# shield.net
KiCad netlist of a schematic drawn in EAGLE
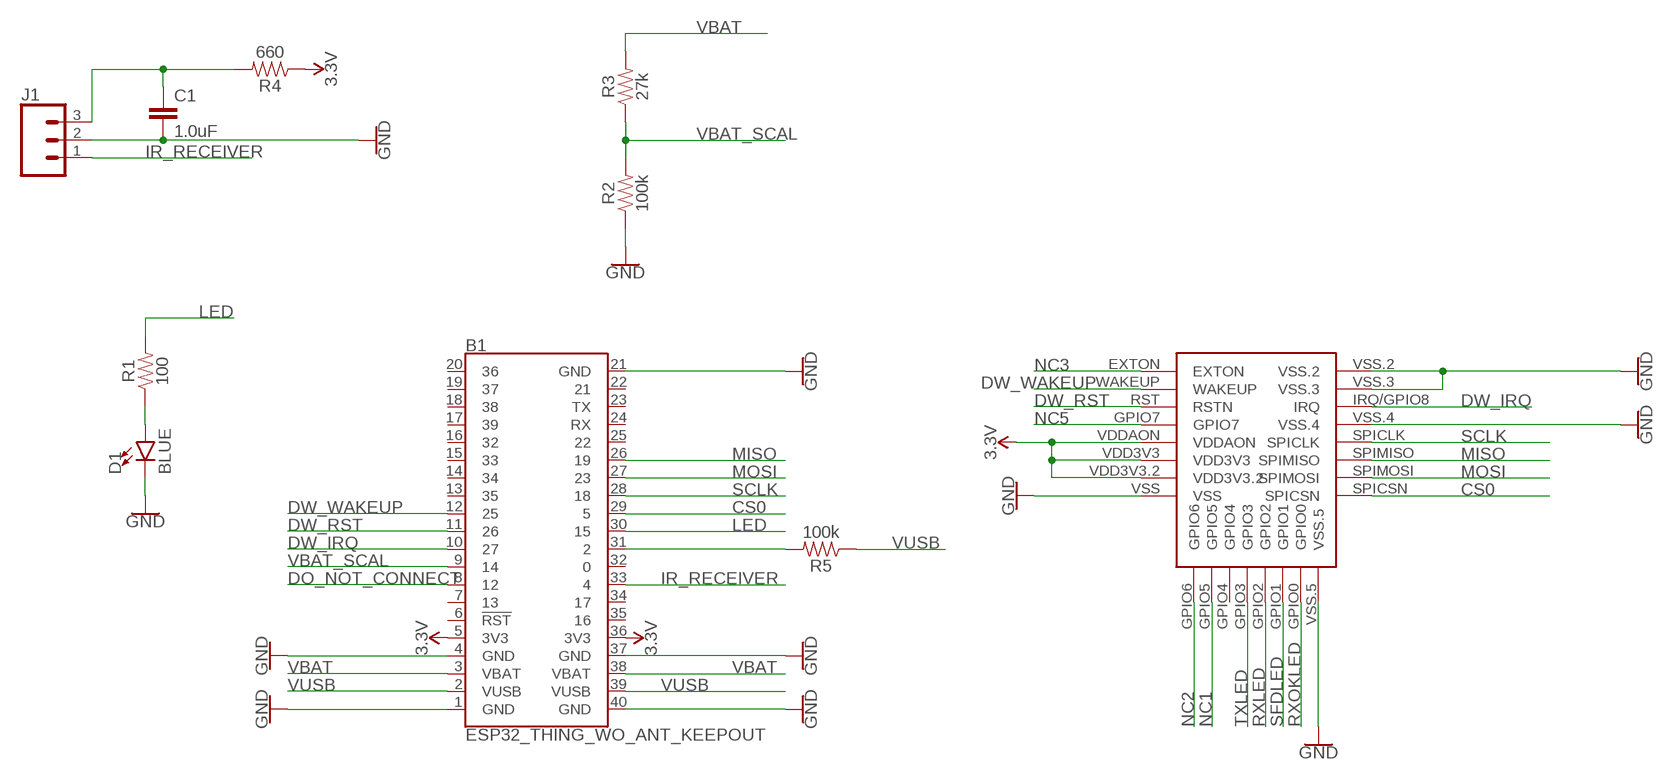
[diagram p0: schematic, sheet 1]

(export (version "E")
  (design (tool "Eeschema 10.0.6"))
  (components
    (comp (ref "B1")
      (value "ESP32_THING_WO_ANT_KEEPOUT")
      (footprint "eagle-import:ESP32_THING_NO_ANT")
      (libsource (lib "eagle-import") (part "ESP32_THING_WO_ANT_KEEPOUT"))
    )
    (comp (ref "C1")
      (value "1.0uF")
      (footprint "eagle-import:1206")
      (libsource (lib "eagle-import") (part "1.0UF-1206-50V-10%"))
    )
    (comp (ref "D1")
      (value "BLUE")
      (footprint "eagle-import:LED-1206")
      (libsource (lib "eagle-import") (part "LED-BLUE1206"))
    )
    (comp (ref "J1")
      (value "CONN_03")
      (footprint "eagle-import:1X03")
      (libsource (lib "eagle-import") (part "CONN_03"))
    )
    (comp (ref "R1")
      (value "100")
      (footprint "eagle-import:1206")
      (libsource (lib "eagle-import") (part "RESISTOR1206"))
    )
    (comp (ref "R2")
      (value "100k")
      (footprint "eagle-import:1206")
      (libsource (lib "eagle-import") (part "RESISTOR1206"))
    )
    (comp (ref "R3")
      (value "27k")
      (footprint "eagle-import:1206")
      (libsource (lib "eagle-import") (part "RESISTOR1206"))
    )
    (comp (ref "R4")
      (value "660")
      (footprint "eagle-import:1206")
      (libsource (lib "eagle-import") (part "RESISTOR1206"))
    )
    (comp (ref "R5")
      (value "100k")
      (footprint "eagle-import:1206")
      (libsource (lib "eagle-import") (part "RESISTOR1206"))
    )
    (comp (ref "U$1")
      (value "DWM1000")
      (footprint "eagle-import:DWM1000")
      (libsource (lib "eagle-import") (part "DWM1000"))
    )
  )
  (nets
    (net (code "1") (name "/CS0") (class "Default")
      (node (ref "B1") (pin "29") (pinfunction "5_29") (pintype "bidirectional"))
      (node (ref "U$1") (pin "SPICSN") (pinfunction "SPICSN_SPICSN") (pintype "bidirectional"))
    )
    (net (code "2") (name "/DO_NOT_CONNECT") (class "Default")
      (node (ref "B1") (pin "8") (pinfunction "12_8") (pintype "bidirectional"))
    )
    (net (code "3") (name "/DW_IRQ") (class "Default")
      (node (ref "B1") (pin "10") (pinfunction "27_10") (pintype "bidirectional"))
      (node (ref "U$1") (pin "IRQ/GPIO8") (pinfunction "IRQ_IRQ/GPIO8") (pintype "bidirectional"))
    )
    (net (code "4") (name "/DW_RST") (class "Default")
      (node (ref "B1") (pin "11") (pinfunction "26_11") (pintype "bidirectional"))
      (node (ref "U$1") (pin "RST") (pinfunction "RSTN_RST") (pintype "bidirectional"))
    )
    (net (code "5") (name "/DW_WAKEUP") (class "Default")
      (node (ref "B1") (pin "12") (pinfunction "25_12") (pintype "bidirectional"))
      (node (ref "U$1") (pin "WAKEUP") (pinfunction "WAKEUP_WAKEUP") (pintype "bidirectional"))
    )
    (net (code "6") (name "/IR_RECEIVER") (class "Default")
      (node (ref "B1") (pin "33") (pinfunction "4_33") (pintype "bidirectional"))
      (node (ref "J1") (pin "1") (pinfunction "1_1") (pintype "passive"))
    )
    (net (code "7") (name "/LED") (class "Default")
      (node (ref "B1") (pin "30") (pinfunction "15_30") (pintype "bidirectional"))
      (node (ref "R1") (pin "2") (pinfunction "2_2") (pintype "passive"))
    )
    (net (code "8") (name "/MISO") (class "Default")
      (node (ref "B1") (pin "26") (pinfunction "19_26") (pintype "bidirectional"))
      (node (ref "U$1") (pin "SPIMISO") (pinfunction "SPIMISO_SPIMISO") (pintype "bidirectional"))
    )
    (net (code "9") (name "/MOSI") (class "Default")
      (node (ref "B1") (pin "27") (pinfunction "23_27") (pintype "bidirectional"))
      (node (ref "U$1") (pin "SPIMOSI") (pinfunction "SPIMOSI_SPIMOSI") (pintype "bidirectional"))
    )
    (net (code "10") (name "/NC1") (class "Default")
      (node (ref "U$1") (pin "GPIO5") (pinfunction "GPIO5_GPIO5") (pintype "bidirectional"))
    )
    (net (code "11") (name "/NC2") (class "Default")
      (node (ref "U$1") (pin "GPIO6") (pinfunction "GPIO6_GPIO6") (pintype "bidirectional"))
    )
    (net (code "12") (name "/NC3") (class "Default")
      (node (ref "U$1") (pin "EXTON") (pinfunction "EXTON_EXTON") (pintype "bidirectional"))
    )
    (net (code "13") (name "/NC5") (class "Default")
      (node (ref "U$1") (pin "GPIO7") (pinfunction "GPIO7_GPIO7") (pintype "bidirectional"))
    )
    (net (code "14") (name "/RXLED") (class "Default")
      (node (ref "U$1") (pin "GPIO2") (pinfunction "GPIO2_GPIO2") (pintype "bidirectional"))
    )
    (net (code "15") (name "/RXOKLED") (class "Default")
      (node (ref "U$1") (pin "GPIO0") (pinfunction "GPIO0_GPIO0") (pintype "bidirectional"))
    )
    (net (code "16") (name "/SCLK") (class "Default")
      (node (ref "B1") (pin "28") (pinfunction "18_28") (pintype "bidirectional"))
      (node (ref "U$1") (pin "SPICLK") (pinfunction "SPICLK_SPICLK") (pintype "bidirectional"))
    )
    (net (code "17") (name "/SFDLED") (class "Default")
      (node (ref "U$1") (pin "GPIO1") (pinfunction "GPIO1_GPIO1") (pintype "bidirectional"))
    )
    (net (code "18") (name "/TXLED") (class "Default")
      (node (ref "U$1") (pin "GPIO3") (pinfunction "GPIO3_GPIO3") (pintype "bidirectional"))
    )
    (net (code "19") (name "/VBAT") (class "Default")
      (node (ref "B1") (pin "3") (pinfunction "VBAT_3") (pintype "bidirectional"))
      (node (ref "B1") (pin "38") (pinfunction "VBAT_38") (pintype "bidirectional"))
      (node (ref "R3") (pin "2") (pinfunction "2_2") (pintype "passive"))
    )
    (net (code "20") (name "/VBAT_SCAL") (class "Default")
      (node (ref "B1") (pin "9") (pinfunction "14_9") (pintype "bidirectional"))
      (node (ref "R2") (pin "2") (pinfunction "2_2") (pintype "passive"))
      (node (ref "R3") (pin "1") (pinfunction "1_1") (pintype "passive"))
    )
    (net (code "21") (name "/VUSB") (class "Default")
      (node (ref "B1") (pin "2") (pinfunction "VUSB_2") (pintype "bidirectional"))
      (node (ref "B1") (pin "39") (pinfunction "VUSB_39") (pintype "bidirectional"))
      (node (ref "R5") (pin "1") (pinfunction "1_1") (pintype "passive"))
    )
    (net (code "22") (name "3.3V") (class "Default")
      (node (ref "B1") (pin "36") (pinfunction "3V3_36") (pintype "bidirectional"))
      (node (ref "B1") (pin "5") (pinfunction "3V3_5") (pintype "bidirectional"))
      (node (ref "R4") (pin "1") (pinfunction "1_1") (pintype "passive"))
      (node (ref "U$1") (pin "VDD3V3") (pinfunction "VDD3V3_VDD3V3") (pintype "bidirectional"))
      (node (ref "U$1") (pin "VDD3V3.2") (pinfunction "VDD3V3.2_VDD3V3.2") (pintype "bidirectional"))
      (node (ref "U$1") (pin "VDDAON") (pinfunction "VDDAON_VDDAON") (pintype "bidirectional"))
    )
    (net (code "23") (name "GND") (class "Default")
      (node (ref "B1") (pin "1") (pinfunction "GND_1") (pintype "bidirectional"))
      (node (ref "B1") (pin "21") (pinfunction "GND_21") (pintype "bidirectional"))
      (node (ref "B1") (pin "37") (pinfunction "GND_37") (pintype "bidirectional"))
      (node (ref "B1") (pin "4") (pinfunction "GND_4") (pintype "bidirectional"))
      (node (ref "B1") (pin "40") (pinfunction "GND_40") (pintype "bidirectional"))
      (node (ref "C1") (pin "2") (pinfunction "2_2") (pintype "passive"))
      (node (ref "D1") (pin "C") (pinfunction "C_C") (pintype "passive"))
      (node (ref "J1") (pin "2") (pinfunction "2_2") (pintype "passive"))
      (node (ref "R2") (pin "1") (pinfunction "1_1") (pintype "passive"))
      (node (ref "U$1") (pin "VSS") (pinfunction "VSS_VSS") (pintype "bidirectional"))
      (node (ref "U$1") (pin "VSS.2") (pinfunction "VSS.2_VSS.2") (pintype "bidirectional"))
      (node (ref "U$1") (pin "VSS.3") (pinfunction "VSS.3_VSS.3") (pintype "bidirectional"))
      (node (ref "U$1") (pin "VSS.4") (pinfunction "VSS.4_VSS.4") (pintype "bidirectional"))
      (node (ref "U$1") (pin "VSS.5") (pinfunction "VSS.5_VSS.5") (pintype "bidirectional"))
    )
    (net (code "24") (name "Net-(B1-2)") (class "Default")
      (node (ref "B1") (pin "31") (pinfunction "2_31") (pintype "bidirectional"))
      (node (ref "R5") (pin "2") (pinfunction "2_2") (pintype "passive"))
    )
    (net (code "25") (name "Net-(C1-Pad1)") (class "Default")
      (node (ref "C1") (pin "1") (pinfunction "1_1") (pintype "passive"))
      (node (ref "J1") (pin "3") (pinfunction "3_3") (pintype "passive"))
      (node (ref "R4") (pin "2") (pinfunction "2_2") (pintype "passive"))
    )
    (net (code "26") (name "Net-(D1-PadA)") (class "Default")
      (node (ref "D1") (pin "A") (pinfunction "A_A") (pintype "passive"))
      (node (ref "R1") (pin "1") (pinfunction "1_1") (pintype "passive"))
    )
    (net (code "27") (name "unconnected-(B1-0-Pad32)") (class "Default")
      (node (ref "B1") (pin "32") (pinfunction "0_32") (pintype "bidirectional"))
    )
    (net (code "28") (name "unconnected-(B1-13-Pad7)") (class "Default")
      (node (ref "B1") (pin "7") (pinfunction "13_7") (pintype "bidirectional"))
    )
    (net (code "29") (name "unconnected-(B1-16-Pad35)") (class "Default")
      (node (ref "B1") (pin "35") (pinfunction "16_35") (pintype "bidirectional"))
    )
    (net (code "30") (name "unconnected-(B1-17-Pad34)") (class "Default")
      (node (ref "B1") (pin "34") (pinfunction "17_34") (pintype "bidirectional"))
    )
    (net (code "31") (name "unconnected-(B1-21-Pad22)") (class "Default")
      (node (ref "B1") (pin "22") (pinfunction "21_22") (pintype "bidirectional"))
    )
    (net (code "32") (name "unconnected-(B1-22-Pad25)") (class "Default")
      (node (ref "B1") (pin "25") (pinfunction "22_25") (pintype "bidirectional"))
    )
    (net (code "33") (name "unconnected-(B1-32-Pad16)") (class "Default")
      (node (ref "B1") (pin "16") (pinfunction "32_16") (pintype "bidirectional"))
    )
    (net (code "34") (name "unconnected-(B1-33-Pad15)") (class "Default")
      (node (ref "B1") (pin "15") (pinfunction "33_15") (pintype "bidirectional"))
    )
    (net (code "35") (name "unconnected-(B1-34-Pad14)") (class "Default")
      (node (ref "B1") (pin "14") (pinfunction "34_14") (pintype "bidirectional"))
    )
    (net (code "36") (name "unconnected-(B1-35-Pad13)") (class "Default")
      (node (ref "B1") (pin "13") (pinfunction "35_13") (pintype "bidirectional"))
    )
    (net (code "37") (name "unconnected-(B1-36-Pad20)") (class "Default")
      (node (ref "B1") (pin "20") (pinfunction "36_20") (pintype "bidirectional"))
    )
    (net (code "38") (name "unconnected-(B1-37-Pad19)") (class "Default")
      (node (ref "B1") (pin "19") (pinfunction "37_19") (pintype "bidirectional"))
    )
    (net (code "39") (name "unconnected-(B1-38-Pad18)") (class "Default")
      (node (ref "B1") (pin "18") (pinfunction "38_18") (pintype "bidirectional"))
    )
    (net (code "40") (name "unconnected-(B1-39-Pad17)") (class "Default")
      (node (ref "B1") (pin "17") (pinfunction "39_17") (pintype "bidirectional"))
    )
    (net (code "41") (name "unconnected-(B1-RX-Pad24)") (class "Default")
      (node (ref "B1") (pin "24") (pinfunction "RX_24") (pintype "bidirectional"))
    )
    (net (code "42") (name "unconnected-(B1-TX-Pad23)") (class "Default")
      (node (ref "B1") (pin "23") (pinfunction "TX_23") (pintype "bidirectional"))
    )
    (net (code "43") (name "unconnected-(B1-~{RST}-Pad6)") (class "Default")
      (node (ref "B1") (pin "6") (pinfunction "~{RST}_6") (pintype "bidirectional"))
    )
    (net (code "44") (name "unconnected-(U$1-PadGPIO4)") (class "Default")
      (node (ref "U$1") (pin "GPIO4") (pinfunction "GPIO4_GPIO4") (pintype "bidirectional"))
    )
  )
)
